# USB_Connector_-_Copy.net
KiCad netlist of a schematic drawn in Altium Designer
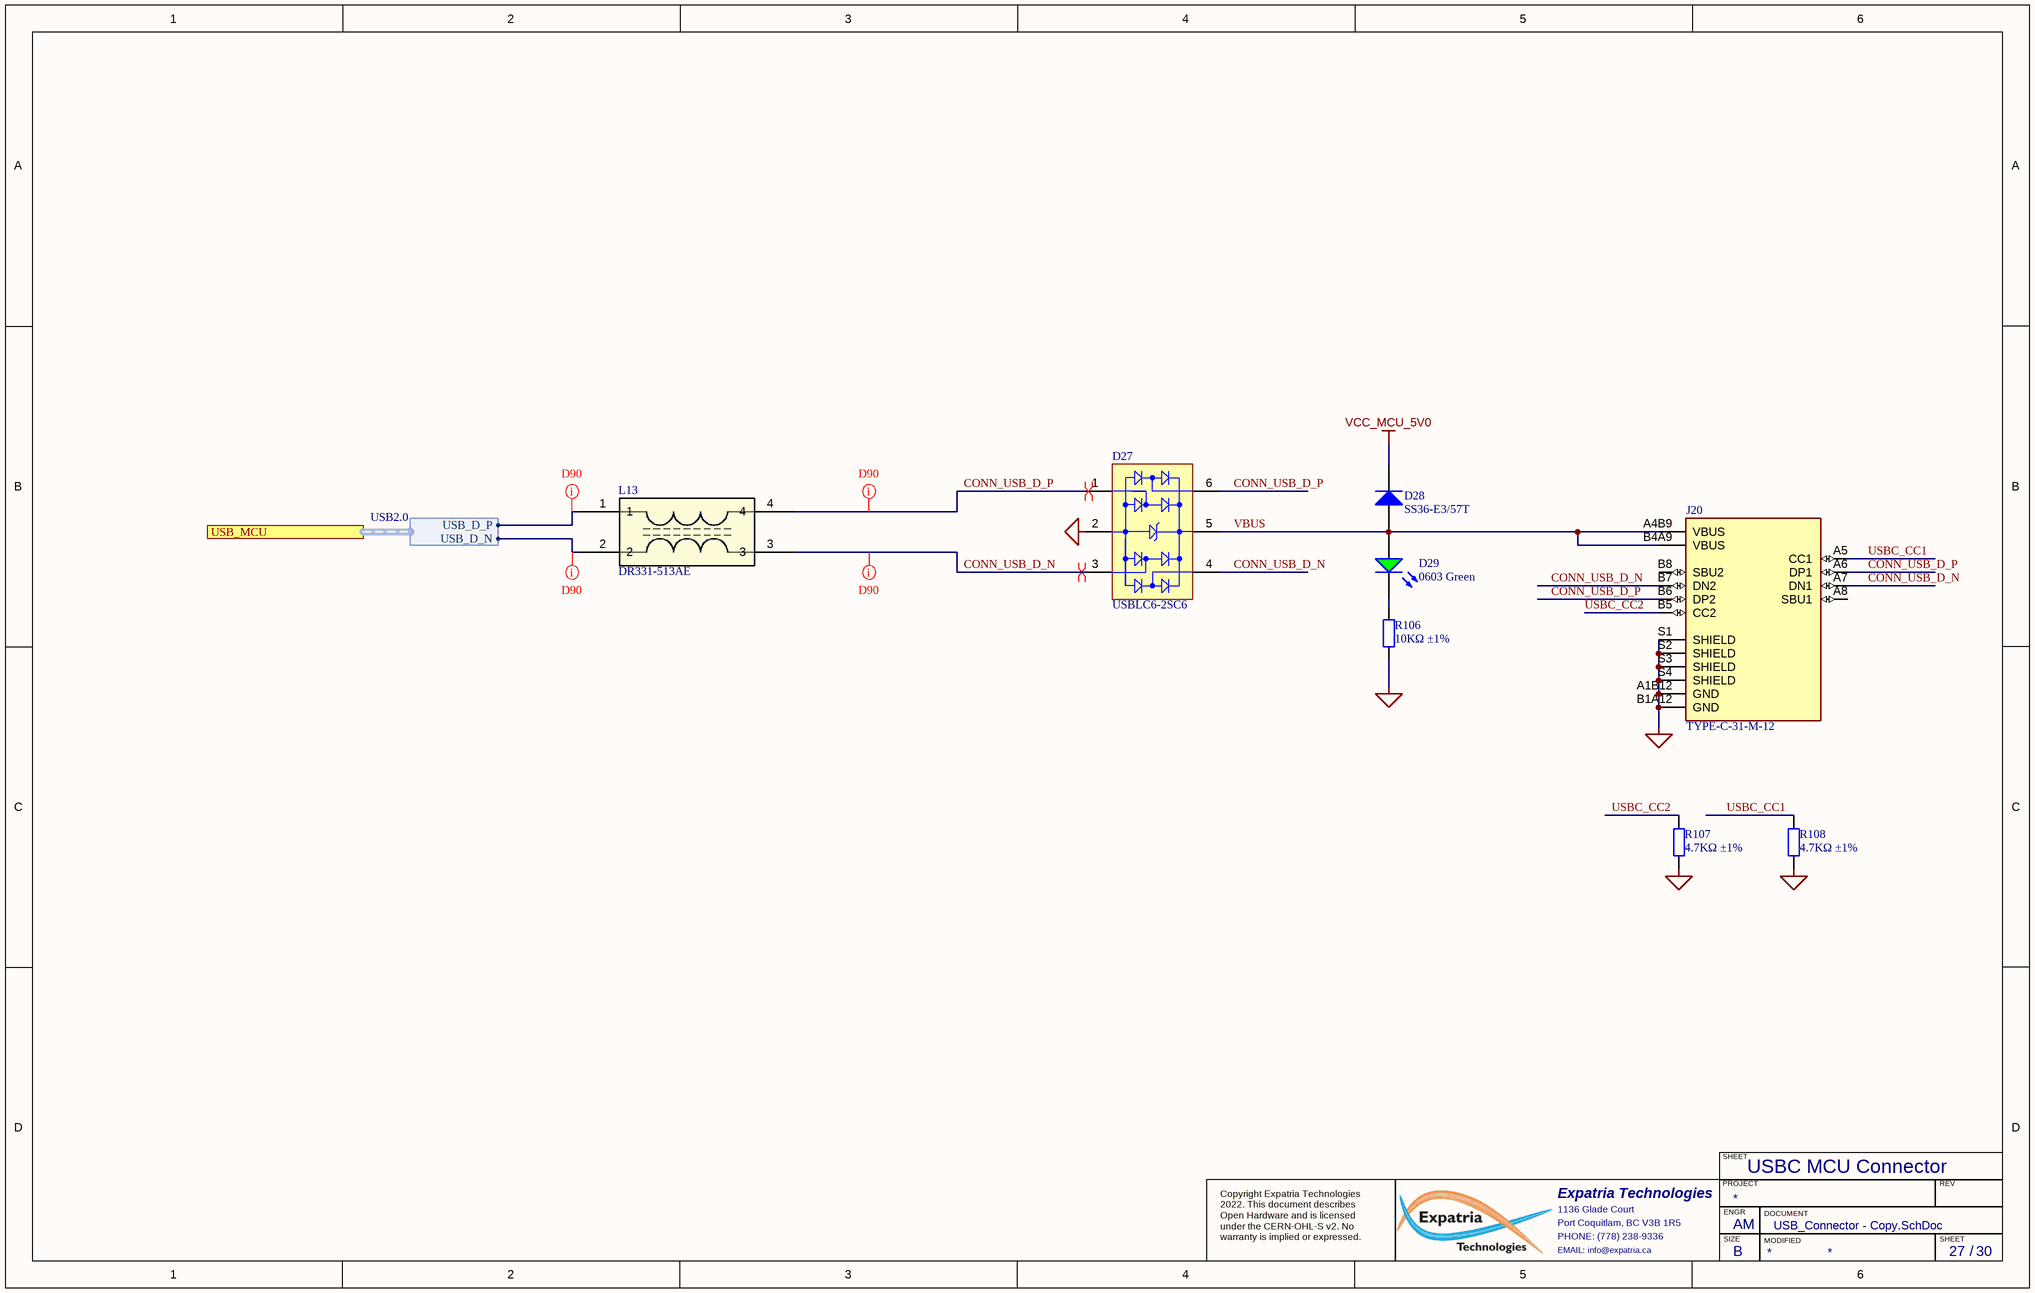
[diagram p0: USB_Connector - Copy.SchDoc]

(export (version "E")
  (design (tool "Eeschema 10.0.6"))
  (components
    (comp (ref "D27")
      (value "USBLC6-2SC6")
      (footprint "SOT95P280X145-6N")
      (description "Very low capacitance ESD protection, 3.5 pF, -40 to 125 degC, 6-Pin SOT23, RoHS, Tape and Reel")
      (fields (field (name "MANUFACTURER") "TECH PUBLIC"))
      (libsource (lib "Sienci_Labs") (part "USBLC6-2SC6"))
    )
    (comp (ref "D28")
      (value "SS36-E3/57T")
      (footprint "SMC(DO-214AB)_S1")
      (description "DIODE SCHOTTKY 60V 3A DO214AB")
      (libsource (lib "Diode") (part "SMC(DO-214AB) SS36-E3/57T"))
    )
    (comp (ref "D29")
      (value "0603 Green")
      (footprint "0603_LED_S1")
      (description "LED")
      (libsource (lib "LED") (part "0603 LED Green"))
    )
    (comp (ref "J20")
      (value "TYPE-C-31-M-12")
      (footprint "HRO_TYPE-C-31-M-12")
      (description "USB Connectors 24 Receptacle 1 8.94*7.3mm RoHS")
      (fields (field (name "MF") "HRO Electronics Co., Ltd."))
      (libsource (lib "Universal_CNC_Breakout") (part "TYPE-C-31-M-12"))
    )
    (comp (ref "L13")
      (value "DR331-513AE")
      (footprint "IND_DR331-513AEE_BRN")
      (description "51 µH @ 100 kHz 2 Line Common Mode Choke Surface Mount 500mA DCR 300mOhm")
      (fields (field (name "MANUFACTURER") "Bourns Electronics"))
      (libsource (lib "Sienci_Labs") (part "DR331-513AE"))
    )
    (comp (ref "R106")
      (value "10KΩ ±1%")
      (footprint "0603_R")
      (description "Chip resistor")
      (fields (field (name "MANUFACTURER") "Uniroyal Elec") (field (name "PARTNUMBER") "0603WAF1002T5E"))
      (libsource (lib "RES") (part "0603 10K (1002) 1%"))
    )
    (comp (ref "R107")
      (value "4.7KΩ ±1%")
      (footprint "0603_R")
      (description "Chip resistor")
      (fields (field (name "MANUFACTURER") "Uniroyal Elec") (field (name "PARTNUMBER") "0603WAF4701T5E"))
      (libsource (lib "RES") (part "0603 4.7K (4701) 1%"))
    )
    (comp (ref "R108")
      (value "4.7KΩ ±1%")
      (footprint "0603_R")
      (description "Chip resistor")
      (fields (field (name "MANUFACTURER") "Uniroyal Elec") (field (name "PARTNUMBER") "0603WAF4701T5E"))
      (libsource (lib "RES") (part "0603 4.7K (4701) 1%"))
    )
  )
  (nets
    (net (code "2") (name "/CONN_USB_D_N") (class "Default")
      (node (ref "D27") (pin "3") (pinfunction "I/O_2_3") (pintype "passive"))
      (node (ref "D27") (pin "4") (pinfunction "I/O_3_4") (pintype "passive"))
      (node (ref "J20") (pin "A7") (pinfunction "DN1_A7") (pintype "bidirectional"))
      (node (ref "J20") (pin "B7") (pinfunction "DN2_B7") (pintype "bidirectional"))
      (node (ref "L13") (pin "3") (pinfunction "3_3") (pintype "passive"))
    )
    (net (code "3") (name "/CONN_USB_D_P") (class "Default")
      (node (ref "D27") (pin "1") (pinfunction "I/O_1_1") (pintype "passive"))
      (node (ref "D27") (pin "6") (pinfunction "I/O_4_6") (pintype "passive"))
      (node (ref "J20") (pin "A6") (pinfunction "DP1_A6") (pintype "bidirectional"))
      (node (ref "J20") (pin "B6") (pinfunction "DP2_B6") (pintype "bidirectional"))
      (node (ref "L13") (pin "4") (pinfunction "4_4") (pintype "passive"))
    )
    (net (code "4") (name "/USBC_CC1") (class "Default")
      (node (ref "J20") (pin "A5") (pinfunction "CC1_A5") (pintype "bidirectional"))
      (node (ref "R108") (pin "1") (pinfunction "1_1") (pintype "passive"))
    )
    (net (code "5") (name "/USBC_CC2") (class "Default")
      (node (ref "J20") (pin "B5") (pinfunction "CC2_B5") (pintype "bidirectional"))
      (node (ref "R107") (pin "1") (pinfunction "1_1") (pintype "passive"))
    )
    (net (code "6") (name "/USB_D_N") (class "Default")
      (node (ref "L13") (pin "2") (pinfunction "2_2") (pintype "passive"))
    )
    (net (code "7") (name "/USB_D_P") (class "Default")
      (node (ref "L13") (pin "1") (pinfunction "1_1") (pintype "passive"))
    )
    (net (code "8") (name "/VBUS") (class "Default")
      (node (ref "D27") (pin "5") (pinfunction "VBUS_5") (pintype "passive"))
      (node (ref "D28") (pin "1") (pinfunction "A_1") (pintype "passive"))
      (node (ref "D29") (pin "A") (pinfunction "A_A") (pintype "passive"))
      (node (ref "J20") (pin "A4B9") (pinfunction "VBUS_A4B9") (pintype "power_in"))
      (node (ref "J20") (pin "B4A9") (pinfunction "VBUS_B4A9") (pintype "power_in"))
    )
    (net (code "10") (name "MCU_GND") (class "Default")
      (node (ref "D27") (pin "2") (pinfunction "GND_2") (pintype "passive"))
      (node (ref "J20") (pin "A1B12") (pinfunction "GND_A1B12") (pintype "power_in"))
      (node (ref "J20") (pin "B1A12") (pinfunction "GND_B1A12") (pintype "power_in"))
      (node (ref "J20") (pin "S1") (pinfunction "SHIELD_S1") (pintype "passive"))
      (node (ref "J20") (pin "S2") (pinfunction "SHIELD_S2") (pintype "passive"))
      (node (ref "J20") (pin "S3") (pinfunction "SHIELD_S3") (pintype "passive"))
      (node (ref "J20") (pin "S4") (pinfunction "SHIELD_S4") (pintype "passive"))
      (node (ref "R106") (pin "1") (pinfunction "1_1") (pintype "passive"))
      (node (ref "R107") (pin "2") (pinfunction "2_2") (pintype "passive"))
      (node (ref "R108") (pin "2") (pinfunction "2_2") (pintype "passive"))
    )
    (net (code "11") (name "Net-(D29-PadK)") (class "Default")
      (node (ref "D29") (pin "K") (pinfunction "K_K") (pintype "passive"))
      (node (ref "R106") (pin "2") (pinfunction "2_2") (pintype "passive"))
    )
    (net (code "12") (name "VCC_MCU_5V0") (class "Default")
      (node (ref "D28") (pin "2") (pinfunction "K_2") (pintype "passive"))
    )
    (net (code "13") (name "unconnected-(J20-SBU1-PadA8)") (class "Default")
      (node (ref "J20") (pin "A8") (pinfunction "SBU1_A8") (pintype "bidirectional"))
    )
    (net (code "14") (name "unconnected-(J20-SBU2-PadB8)") (class "Default")
      (node (ref "J20") (pin "B8") (pinfunction "SBU2_B8") (pintype "bidirectional"))
    )
  )
)
